# Tugas_Gambar_teknik_1_Rizqulloh_Faathir_.net
KiCad netlist of a schematic drawn in EAGLE
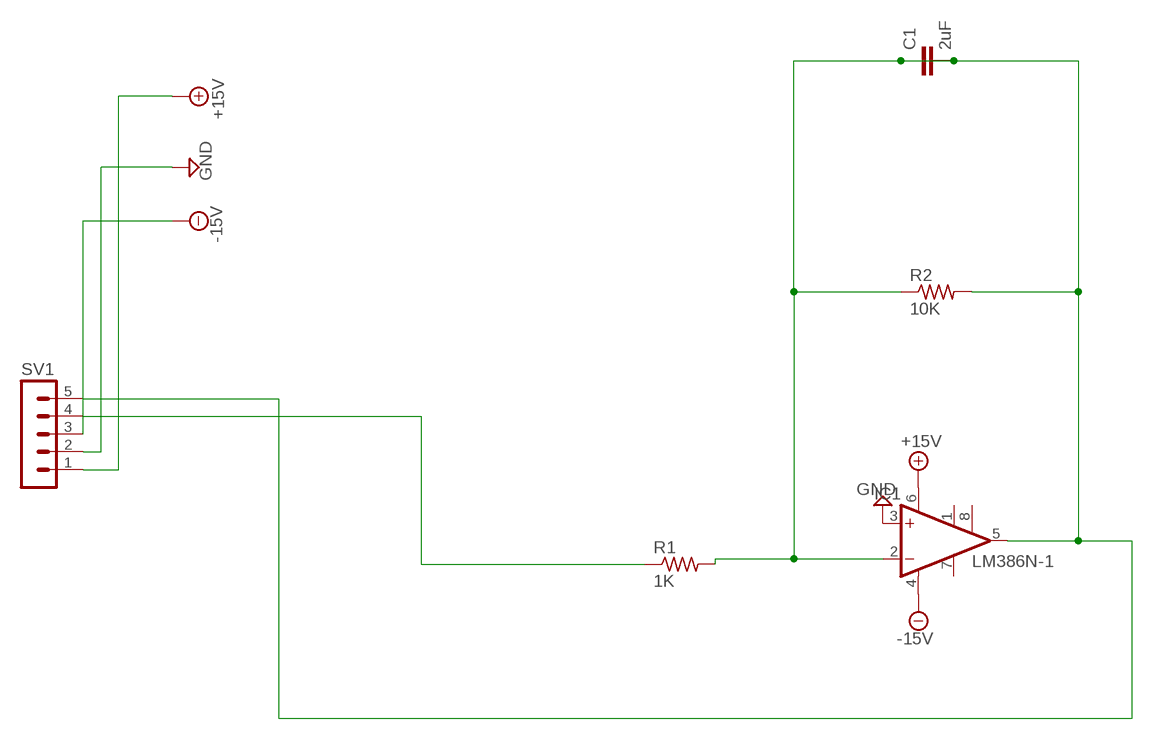
[diagram p0: schematic, sheet 1]

(export (version "E")
  (design (tool "Eeschema 10.0.6"))
  (components
    (comp (ref "C1")
      (value "2uF")
      (footprint "eagle-import:C025-024X044")
      (libsource (lib "eagle-import") (part "C-EU025-024X044"))
    )
    (comp (ref "IC1")
      (value "LM386N-1")
      (footprint "eagle-import:DIL08")
      (libsource (lib "eagle-import") (part "LM386?-N1"))
    )
    (comp (ref "R1")
      (value "1K")
      (footprint "eagle-import:0204V")
      (libsource (lib "eagle-import") (part "R-US_0204/2V"))
    )
    (comp (ref "R2")
      (value "10K")
      (footprint "eagle-import:0204V")
      (libsource (lib "eagle-import") (part "R-US_0204/2V"))
    )
    (comp (ref "SV1")
      (value "MA05-1")
      (footprint "eagle-import:MA05-1")
      (libsource (lib "eagle-import") (part "MA05-1"))
    )
  )
  (nets
    (net (code "1") (name "+15V") (class "Default")
      (node (ref "IC1") (pin "6") (pinfunction "VS_6") (pintype "power_in"))
      (node (ref "SV1") (pin "1") (pinfunction "1_1") (pintype "passive"))
    )
    (net (code "2") (name "-15V") (class "Default")
      (node (ref "IC1") (pin "4") (pinfunction "GND_4") (pintype "power_in"))
      (node (ref "SV1") (pin "3") (pinfunction "3_3") (pintype "passive"))
    )
    (net (code "3") (name "GND") (class "Default")
      (node (ref "IC1") (pin "3") (pinfunction "+IN_3") (pintype "input"))
      (node (ref "SV1") (pin "2") (pinfunction "2_2") (pintype "passive"))
    )
    (net (code "4") (name "Net-(IC1--IN)") (class "Default")
      (node (ref "C1") (pin "1") (pinfunction "1_1") (pintype "passive"))
      (node (ref "C1") (pin "2") (pinfunction "2_2") (pintype "passive"))
      (node (ref "IC1") (pin "2") (pinfunction "-IN_2") (pintype "input"))
      (node (ref "IC1") (pin "5") (pinfunction "OUT_5") (pintype "output"))
      (node (ref "R1") (pin "2") (pinfunction "2_2") (pintype "passive"))
      (node (ref "R2") (pin "1") (pinfunction "1_1") (pintype "passive"))
      (node (ref "R2") (pin "2") (pinfunction "2_2") (pintype "passive"))
      (node (ref "SV1") (pin "5") (pinfunction "5_5") (pintype "passive"))
    )
    (net (code "5") (name "Net-(R1-Pad1)") (class "Default")
      (node (ref "R1") (pin "1") (pinfunction "1_1") (pintype "passive"))
      (node (ref "SV1") (pin "4") (pinfunction "4_4") (pintype "passive"))
    )
    (net (code "6") (name "unconnected-(IC1-BYPASS-Pad7)") (class "Default")
      (node (ref "IC1") (pin "7") (pinfunction "BYPASS_7") (pintype "passive"))
    )
    (net (code "7") (name "unconnected-(IC1-GAIN-Pad1)") (class "Default")
      (node (ref "IC1") (pin "1") (pinfunction "GAIN_1") (pintype "passive"))
    )
    (net (code "8") (name "unconnected-(IC1-GAIN-Pad8)") (class "Default")
      (node (ref "IC1") (pin "8") (pinfunction "GAIN_8") (pintype "passive"))
    )
  )
)
